# Raspberry_Pi_Circuit_Board_2.net
KiCad netlist of a schematic drawn in EAGLE
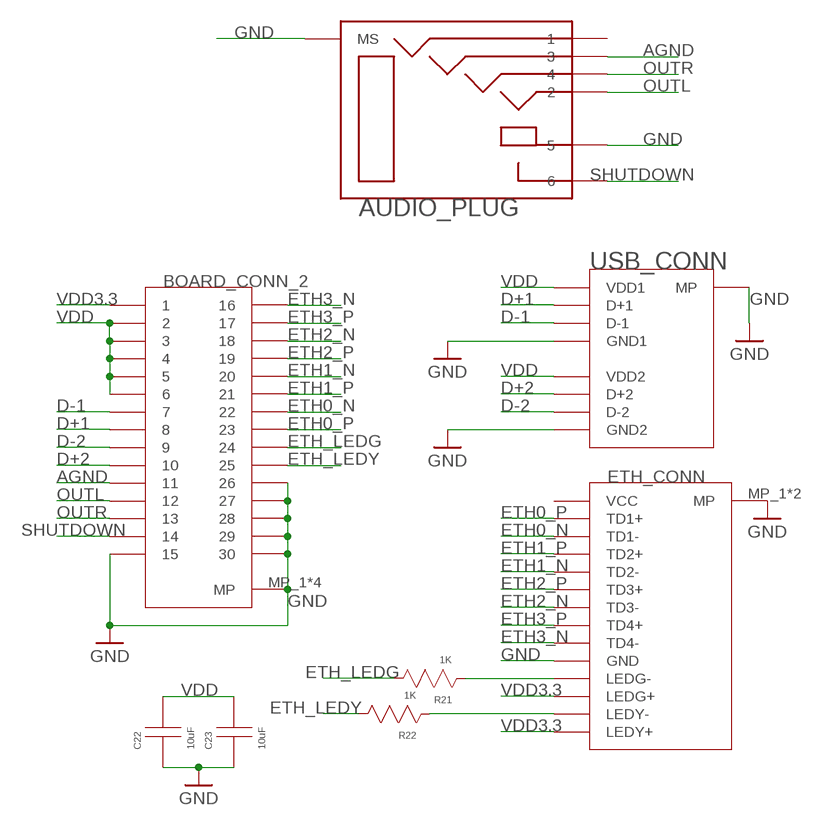
[diagram p0: schematic, sheet 1]

(export (version "E")
  (design (tool "Eeschema 10.0.6"))
  (components
    (comp (ref "AUDIO_PLUG")
      (value "AUDIOPLUG-ASJ-192-Y-TR")
      (footprint "eagle-import:AUDIOPLUG-ASJ-192-Y-TR")
      (libsource (lib "eagle-import") (part "AUDIOPLUG-ASJ-192-Y-TR"))
    )
    (comp (ref "BOARD_CONN_2")
      (value "MEZZANINE-AXT530124")
      (footprint "eagle-import:MEZZANINE-AXT530124")
      (libsource (lib "eagle-import") (part "MEZZANINE-AXT530124"))
    )
    (comp (ref "C22")
      (value "10uF")
      (footprint "eagle-import:CAP-603")
      (libsource (lib "eagle-import") (part "CAP-603"))
    )
    (comp (ref "C23")
      (value "10uF")
      (footprint "eagle-import:CAP-603")
      (libsource (lib "eagle-import") (part "CAP-603"))
    )
    (comp (ref "ETH_CONN")
      (value "ETH-GLPLX-SMT-188S7-QQ-Y/G")
      (footprint "eagle-import:ETH-GLPLX-SMT-188S7-QQ-Y_G")
      (libsource (lib "eagle-import") (part "ETH-GLPLX-SMT-188S7-QQ-Y/G"))
    )
    (comp (ref "R21")
      (value "1K")
      (footprint "eagle-import:RES-603")
      (libsource (lib "eagle-import") (part "RES-603"))
    )
    (comp (ref "R22")
      (value "1K")
      (footprint "eagle-import:RES-603")
      (libsource (lib "eagle-import") (part "RES-603"))
    )
    (comp (ref "USB_CONN")
      (value "USB-614108646521")
      (footprint "eagle-import:USB-614108646521")
      (libsource (lib "eagle-import") (part "USB-614108646521"))
    )
  )
  (nets
    (net (code "1") (name "/AGND") (class "Default")
      (node (ref "AUDIO_PLUG") (pin "3") (pinfunction "3_3") (pintype "bidirectional"))
      (node (ref "BOARD_CONN_2") (pin "11") (pinfunction "11_11") (pintype "bidirectional"))
    )
    (net (code "2") (name "/D+1") (class "Default")
      (node (ref "BOARD_CONN_2") (pin "8") (pinfunction "8_8") (pintype "bidirectional"))
      (node (ref "USB_CONN") (pin "D+1") (pinfunction "D+1_D+1") (pintype "bidirectional"))
    )
    (net (code "3") (name "/D+2") (class "Default")
      (node (ref "BOARD_CONN_2") (pin "10") (pinfunction "10_10") (pintype "bidirectional"))
      (node (ref "USB_CONN") (pin "D+2") (pinfunction "D+2_D+2") (pintype "bidirectional"))
    )
    (net (code "4") (name "/D-1") (class "Default")
      (node (ref "BOARD_CONN_2") (pin "7") (pinfunction "7_7") (pintype "bidirectional"))
      (node (ref "USB_CONN") (pin "D-1") (pinfunction "D-1_D-1") (pintype "bidirectional"))
    )
    (net (code "5") (name "/D-2") (class "Default")
      (node (ref "BOARD_CONN_2") (pin "9") (pinfunction "9_9") (pintype "bidirectional"))
      (node (ref "USB_CONN") (pin "D-2") (pinfunction "D-2_D-2") (pintype "bidirectional"))
    )
    (net (code "6") (name "/ETH0_N") (class "Default")
      (node (ref "BOARD_CONN_2") (pin "22") (pinfunction "22_22") (pintype "bidirectional"))
      (node (ref "ETH_CONN") (pin "TD1-") (pinfunction "TD1-_TD1-") (pintype "bidirectional"))
    )
    (net (code "7") (name "/ETH0_P") (class "Default")
      (node (ref "BOARD_CONN_2") (pin "23") (pinfunction "23_23") (pintype "bidirectional"))
      (node (ref "ETH_CONN") (pin "TD1+") (pinfunction "TD1+_TD1+") (pintype "bidirectional"))
    )
    (net (code "8") (name "/ETH1_N") (class "Default")
      (node (ref "BOARD_CONN_2") (pin "20") (pinfunction "20_20") (pintype "bidirectional"))
      (node (ref "ETH_CONN") (pin "TD2-") (pinfunction "TD2-_TD2-") (pintype "bidirectional"))
    )
    (net (code "9") (name "/ETH1_P") (class "Default")
      (node (ref "BOARD_CONN_2") (pin "21") (pinfunction "21_21") (pintype "bidirectional"))
      (node (ref "ETH_CONN") (pin "TD2+") (pinfunction "TD2+_TD2+") (pintype "bidirectional"))
    )
    (net (code "10") (name "/ETH2_N") (class "Default")
      (node (ref "BOARD_CONN_2") (pin "18") (pinfunction "18_18") (pintype "bidirectional"))
      (node (ref "ETH_CONN") (pin "TD3-") (pinfunction "TD3-_TD3-") (pintype "bidirectional"))
    )
    (net (code "11") (name "/ETH2_P") (class "Default")
      (node (ref "BOARD_CONN_2") (pin "19") (pinfunction "19_19") (pintype "bidirectional"))
      (node (ref "ETH_CONN") (pin "TD3+") (pinfunction "TD3+_TD3+") (pintype "bidirectional"))
    )
    (net (code "12") (name "/ETH3_N") (class "Default")
      (node (ref "BOARD_CONN_2") (pin "16") (pinfunction "16_16") (pintype "bidirectional"))
      (node (ref "ETH_CONN") (pin "TD4-") (pinfunction "TD4-_TD4-") (pintype "bidirectional"))
    )
    (net (code "13") (name "/ETH3_P") (class "Default")
      (node (ref "BOARD_CONN_2") (pin "17") (pinfunction "17_17") (pintype "bidirectional"))
      (node (ref "ETH_CONN") (pin "TD4+") (pinfunction "TD4+_TD4+") (pintype "bidirectional"))
    )
    (net (code "14") (name "/ETH_LEDG") (class "Default")
      (node (ref "BOARD_CONN_2") (pin "24") (pinfunction "24_24") (pintype "bidirectional"))
      (node (ref "R21") (pin "C") (pinfunction "C_C") (pintype "bidirectional"))
    )
    (net (code "15") (name "/ETH_LEDY") (class "Default")
      (node (ref "BOARD_CONN_2") (pin "25") (pinfunction "25_25") (pintype "bidirectional"))
      (node (ref "R22") (pin "C") (pinfunction "C_C") (pintype "bidirectional"))
    )
    (net (code "16") (name "/OUTL") (class "Default")
      (node (ref "AUDIO_PLUG") (pin "2") (pinfunction "2_2") (pintype "bidirectional"))
      (node (ref "BOARD_CONN_2") (pin "12") (pinfunction "12_12") (pintype "bidirectional"))
    )
    (net (code "17") (name "/OUTR") (class "Default")
      (node (ref "AUDIO_PLUG") (pin "4") (pinfunction "4_4") (pintype "bidirectional"))
      (node (ref "BOARD_CONN_2") (pin "13") (pinfunction "13_13") (pintype "bidirectional"))
    )
    (net (code "18") (name "/SHUTDOWN") (class "Default")
      (node (ref "AUDIO_PLUG") (pin "6") (pinfunction "6_6") (pintype "bidirectional"))
      (node (ref "BOARD_CONN_2") (pin "14") (pinfunction "14_14") (pintype "bidirectional"))
    )
    (net (code "19") (name "/VDD") (class "Default")
      (node (ref "BOARD_CONN_2") (pin "2") (pinfunction "2_2") (pintype "bidirectional"))
      (node (ref "BOARD_CONN_2") (pin "3") (pinfunction "3_3") (pintype "bidirectional"))
      (node (ref "BOARD_CONN_2") (pin "4") (pinfunction "4_4") (pintype "bidirectional"))
      (node (ref "BOARD_CONN_2") (pin "5") (pinfunction "5_5") (pintype "bidirectional"))
      (node (ref "BOARD_CONN_2") (pin "6") (pinfunction "6_6") (pintype "bidirectional"))
      (node (ref "C22") (pin "C") (pinfunction "C_C") (pintype "bidirectional"))
      (node (ref "C23") (pin "C") (pinfunction "C_C") (pintype "bidirectional"))
      (node (ref "USB_CONN") (pin "VDD1") (pinfunction "VDD1_VDD1") (pintype "bidirectional"))
      (node (ref "USB_CONN") (pin "VDD2") (pinfunction "VDD2_VDD2") (pintype "bidirectional"))
    )
    (net (code "20") (name "/VDD3.3") (class "Default")
      (node (ref "BOARD_CONN_2") (pin "1") (pinfunction "1_1") (pintype "bidirectional"))
      (node (ref "ETH_CONN") (pin "LEDG+") (pinfunction "LEDG+_LEDG+") (pintype "bidirectional"))
      (node (ref "ETH_CONN") (pin "LEDY+") (pinfunction "LEDY+_LEDY+") (pintype "bidirectional"))
    )
    (net (code "21") (name "GND") (class "Default")
      (node (ref "AUDIO_PLUG") (pin "5") (pinfunction "5_5") (pintype "bidirectional"))
      (node (ref "AUDIO_PLUG") (pin "MS1") (pinfunction "MS_MS1") (pintype "bidirectional"))
      (node (ref "AUDIO_PLUG") (pin "MS2") (pinfunction "MS_MS2") (pintype "bidirectional"))
      (node (ref "BOARD_CONN_2") (pin "15") (pinfunction "15_15") (pintype "bidirectional"))
      (node (ref "BOARD_CONN_2") (pin "26") (pinfunction "26_26") (pintype "bidirectional"))
      (node (ref "BOARD_CONN_2") (pin "27") (pinfunction "27_27") (pintype "bidirectional"))
      (node (ref "BOARD_CONN_2") (pin "28") (pinfunction "28_28") (pintype "bidirectional"))
      (node (ref "BOARD_CONN_2") (pin "29") (pinfunction "29_29") (pintype "bidirectional"))
      (node (ref "BOARD_CONN_2") (pin "30") (pinfunction "30_30") (pintype "bidirectional"))
      (node (ref "BOARD_CONN_2") (pin "MP_1") (pinfunction "MP_MP_1") (pintype "bidirectional"))
      (node (ref "BOARD_CONN_2") (pin "MP_2") (pinfunction "MP_MP_2") (pintype "bidirectional"))
      (node (ref "BOARD_CONN_2") (pin "MP_3") (pinfunction "MP_MP_3") (pintype "bidirectional"))
      (node (ref "BOARD_CONN_2") (pin "MP_4") (pinfunction "MP_MP_4") (pintype "bidirectional"))
      (node (ref "C22") (pin "A") (pinfunction "A_A") (pintype "bidirectional"))
      (node (ref "C23") (pin "A") (pinfunction "A_A") (pintype "bidirectional"))
      (node (ref "ETH_CONN") (pin "GND") (pinfunction "GND_GND") (pintype "bidirectional"))
      (node (ref "ETH_CONN") (pin "MP_1") (pinfunction "MP_MP_1") (pintype "bidirectional"))
      (node (ref "ETH_CONN") (pin "MP_2") (pinfunction "MP_MP_2") (pintype "bidirectional"))
      (node (ref "USB_CONN") (pin "GND1") (pinfunction "GND1_GND1") (pintype "bidirectional"))
      (node (ref "USB_CONN") (pin "GND2") (pinfunction "GND2_GND2") (pintype "bidirectional"))
      (node (ref "USB_CONN") (pin "MP_1") (pinfunction "MP_MP_1") (pintype "bidirectional"))
      (node (ref "USB_CONN") (pin "MP_2") (pinfunction "MP_MP_2") (pintype "bidirectional"))
      (node (ref "USB_CONN") (pin "MP_3") (pinfunction "MP_MP_3") (pintype "bidirectional"))
      (node (ref "USB_CONN") (pin "MP_4") (pinfunction "MP_MP_4") (pintype "bidirectional"))
    )
    (net (code "22") (name "Net-(ETH_CONN-PadLEDG-)") (class "Default")
      (node (ref "ETH_CONN") (pin "LEDG-") (pinfunction "LEDG-_LEDG-") (pintype "bidirectional"))
      (node (ref "R21") (pin "A") (pinfunction "A_A") (pintype "bidirectional"))
    )
    (net (code "23") (name "Net-(ETH_CONN-PadLEDY-)") (class "Default")
      (node (ref "ETH_CONN") (pin "LEDY-") (pinfunction "LEDY-_LEDY-") (pintype "bidirectional"))
      (node (ref "R22") (pin "A") (pinfunction "A_A") (pintype "bidirectional"))
    )
    (net (code "24") (name "unconnected-(AUDIO_PLUG-Pad1)") (class "Default")
      (node (ref "AUDIO_PLUG") (pin "1") (pinfunction "1_1") (pintype "bidirectional"))
    )
    (net (code "25") (name "unconnected-(ETH_CONN-PadVCC)") (class "Default")
      (node (ref "ETH_CONN") (pin "VCC") (pinfunction "VCC_VCC") (pintype "bidirectional"))
    )
  )
)
